# meccano_micro.net
KiCad netlist of a schematic drawn in EAGLE
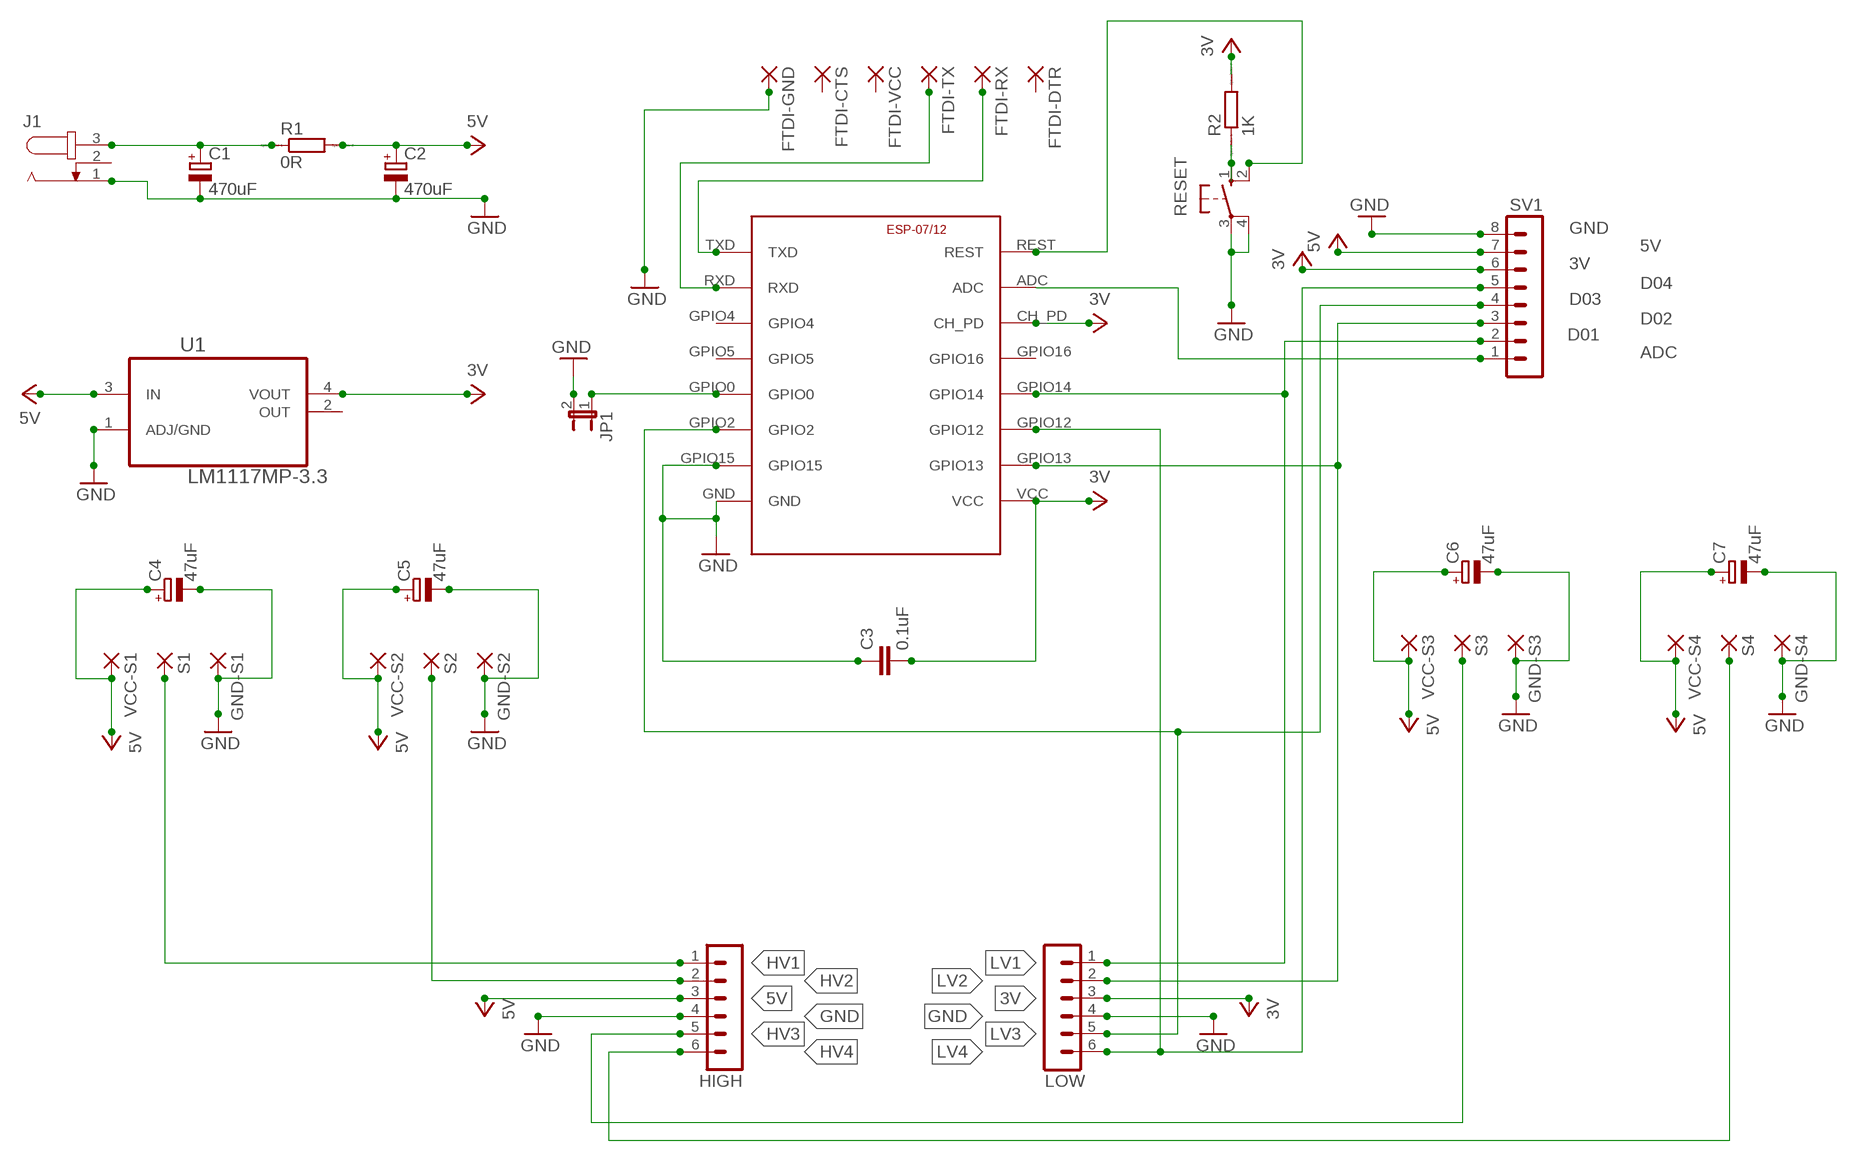
[diagram p0: schematic, sheet 1]

(export (version "E")
  (design (tool "Eeschema 10.0.6"))
  (components
    (comp (ref "C1")
      (value "470uF")
      (footprint "eagle-import:B45181B")
      (libsource (lib "eagle-import") (part "CPOL-EUB45181B"))
    )
    (comp (ref "C2")
      (value "470uF")
      (footprint "eagle-import:B45181B")
      (libsource (lib "eagle-import") (part "CPOL-EUB45181B"))
    )
    (comp (ref "C3")
      (value "0.1uF")
      (footprint "eagle-import:C2.5-4")
      (libsource (lib "eagle-import") (part "C2.5/4"))
    )
    (comp (ref "C4")
      (value "47uF")
      (footprint "eagle-import:B45181B")
      (libsource (lib "eagle-import") (part "CPOL-EUB45181B"))
    )
    (comp (ref "C5")
      (value "47uF")
      (footprint "eagle-import:B45181B")
      (libsource (lib "eagle-import") (part "CPOL-EUB45181B"))
    )
    (comp (ref "C6")
      (value "47uF")
      (footprint "eagle-import:B45181B")
      (libsource (lib "eagle-import") (part "CPOL-EUB45181B"))
    )
    (comp (ref "C7")
      (value "47uF")
      (footprint "eagle-import:B45181B")
      (libsource (lib "eagle-import") (part "CPOL-EUB45181B"))
    )
    (comp (ref "ESP-07/12")
      (value "ESP8266-07")
      (footprint "eagle-import:ESP-07")
      (libsource (lib "eagle-import") (part "ESP8266-07"))
    )
    (comp (ref "FTDI-CTS")
      (value "1,6/0,8")
      (footprint "eagle-import:1,6_0,8")
      (libsource (lib "eagle-import") (part "1,6/0,8"))
    )
    (comp (ref "FTDI-DTR")
      (value "1,6/0,8")
      (footprint "eagle-import:1,6_0,8")
      (libsource (lib "eagle-import") (part "1,6/0,8"))
    )
    (comp (ref "FTDI-GND")
      (value "1,6/0,8")
      (footprint "eagle-import:1,6_0,8")
      (libsource (lib "eagle-import") (part "1,6/0,8"))
    )
    (comp (ref "FTDI-RX")
      (value "1,6/0,8")
      (footprint "eagle-import:1,6_0,8")
      (libsource (lib "eagle-import") (part "1,6/0,8"))
    )
    (comp (ref "FTDI-TX")
      (value "1,6/0,8")
      (footprint "eagle-import:1,6_0,8")
      (libsource (lib "eagle-import") (part "1,6/0,8"))
    )
    (comp (ref "FTDI-VCC")
      (value "1,6/0,8")
      (footprint "eagle-import:1,6_0,8")
      (libsource (lib "eagle-import") (part "1,6/0,8"))
    )
    (comp (ref "GND-S1")
      (value "1,6/0,8")
      (footprint "eagle-import:1,6_0,8")
      (libsource (lib "eagle-import") (part "1,6/0,8"))
    )
    (comp (ref "GND-S2")
      (value "1,6/0,8")
      (footprint "eagle-import:1,6_0,8")
      (libsource (lib "eagle-import") (part "1,6/0,8"))
    )
    (comp (ref "GND-S3")
      (value "1,6/0,8")
      (footprint "eagle-import:1,6_0,8")
      (libsource (lib "eagle-import") (part "1,6/0,8"))
    )
    (comp (ref "GND-S4")
      (value "1,6/0,8")
      (footprint "eagle-import:1,6_0,8")
      (libsource (lib "eagle-import") (part "1,6/0,8"))
    )
    (comp (ref "HIGH")
      (value "MA06-1")
      (footprint "eagle-import:MA06-1")
      (libsource (lib "eagle-import") (part "MA06-1"))
    )
    (comp (ref "J1")
      (value "JACK-PLUG0")
      (footprint "eagle-import:SPC4077")
      (libsource (lib "eagle-import") (part "JACK-PLUG0"))
    )
    (comp (ref "JP1")
      (value "JP1E")
      (footprint "eagle-import:JP1")
      (libsource (lib "eagle-import") (part "JP1E"))
    )
    (comp (ref "LOW")
      (value "MA06-1")
      (footprint "eagle-import:MA06-1")
      (libsource (lib "eagle-import") (part "MA06-1"))
    )
    (comp (ref "R1")
      (value "0R")
      (footprint "eagle-import:0204_7")
      (libsource (lib "eagle-import") (part "R0204/7"))
    )
    (comp (ref "R2")
      (value "1K")
      (footprint "eagle-import:0204_7")
      (libsource (lib "eagle-import") (part "R0204/7"))
    )
    (comp (ref "RESET")
      (value "10-XX")
      (footprint "eagle-import:B3F-10XX")
      (fields (field (name "MPN") "B3F-1000"))
      (libsource (lib "eagle-import") (part "10-XX"))
    )
    (comp (ref "S1")
      (value "1,6/0,8")
      (footprint "eagle-import:1,6_0,8")
      (libsource (lib "eagle-import") (part "1,6/0,8"))
    )
    (comp (ref "S2")
      (value "1,6/0,8")
      (footprint "eagle-import:1,6_0,8")
      (libsource (lib "eagle-import") (part "1,6/0,8"))
    )
    (comp (ref "S3")
      (value "1,6/0,8")
      (footprint "eagle-import:1,6_0,8")
      (libsource (lib "eagle-import") (part "1,6/0,8"))
    )
    (comp (ref "S4")
      (value "1,6/0,8")
      (footprint "eagle-import:1,6_0,8")
      (libsource (lib "eagle-import") (part "1,6/0,8"))
    )
    (comp (ref "SV1")
      (value "MA08-1")
      (footprint "eagle-import:MA08-1")
      (libsource (lib "eagle-import") (part "MA08-1"))
    )
    (comp (ref "U1")
      (value "LM1117MP-3.3")
      (footprint "eagle-import:SOT230P696X180-4N")
      (libsource (lib "eagle-import") (part "LM1117MP-3.3"))
    )
    (comp (ref "VCC-S1")
      (value "1,6/0,8")
      (footprint "eagle-import:1,6_0,8")
      (libsource (lib "eagle-import") (part "1,6/0,8"))
    )
    (comp (ref "VCC-S2")
      (value "1,6/0,8")
      (footprint "eagle-import:1,6_0,8")
      (libsource (lib "eagle-import") (part "1,6/0,8"))
    )
    (comp (ref "VCC-S3")
      (value "1,6/0,8")
      (footprint "eagle-import:1,6_0,8")
      (libsource (lib "eagle-import") (part "1,6/0,8"))
    )
    (comp (ref "VCC-S4")
      (value "1,6/0,8")
      (footprint "eagle-import:1,6_0,8")
      (libsource (lib "eagle-import") (part "1,6/0,8"))
    )
  )
  (nets
    (net (code "1") (name "3V") (class "Default")
      (node (ref "C3") (pin "2") (pinfunction "2_2") (pintype "passive"))
      (node (ref "ESP-07/12") (pin "CH_PD") (pinfunction "CH_PD_CH_PD") (pintype "input"))
      (node (ref "ESP-07/12") (pin "VCC") (pinfunction "VCC_VCC") (pintype "power_in"))
      (node (ref "LOW") (pin "3") (pinfunction "3_3") (pintype "passive"))
      (node (ref "R2") (pin "1") (pinfunction "1_1") (pintype "passive"))
      (node (ref "R2") (pin "2") (pinfunction "2_2") (pintype "passive"))
      (node (ref "RESET") (pin "1") (pinfunction "S_1") (pintype "passive"))
      (node (ref "SV1") (pin "6") (pinfunction "6_6") (pintype "passive"))
      (node (ref "U1") (pin "4") (pinfunction "VOUT_4") (pintype "output"))
    )
    (net (code "2") (name "5V") (class "Default")
      (node (ref "C2") (pin "+") (pinfunction "+_+") (pintype "passive"))
      (node (ref "C4") (pin "+") (pinfunction "+_+") (pintype "passive"))
      (node (ref "C5") (pin "+") (pinfunction "+_+") (pintype "passive"))
      (node (ref "C6") (pin "+") (pinfunction "+_+") (pintype "passive"))
      (node (ref "C7") (pin "+") (pinfunction "+_+") (pintype "passive"))
      (node (ref "HIGH") (pin "3") (pinfunction "3_3") (pintype "passive"))
      (node (ref "R1") (pin "2") (pinfunction "2_2") (pintype "passive"))
      (node (ref "SV1") (pin "7") (pinfunction "7_7") (pintype "passive"))
      (node (ref "U1") (pin "3") (pinfunction "IN_3") (pintype "input"))
      (node (ref "VCC-S1") (pin "1") (pinfunction "P_1") (pintype "passive"))
      (node (ref "VCC-S2") (pin "1") (pinfunction "P_1") (pintype "passive"))
      (node (ref "VCC-S3") (pin "1") (pinfunction "P_1") (pintype "passive"))
      (node (ref "VCC-S4") (pin "1") (pinfunction "P_1") (pintype "passive"))
    )
    (net (code "3") (name "GND") (class "Default")
      (node (ref "C1") (pin "-") (pinfunction "-_-") (pintype "passive"))
      (node (ref "C2") (pin "-") (pinfunction "-_-") (pintype "passive"))
      (node (ref "C3") (pin "1") (pinfunction "1_1") (pintype "passive"))
      (node (ref "C4") (pin "-") (pinfunction "-_-") (pintype "passive"))
      (node (ref "C5") (pin "-") (pinfunction "-_-") (pintype "passive"))
      (node (ref "C6") (pin "-") (pinfunction "-_-") (pintype "passive"))
      (node (ref "C7") (pin "-") (pinfunction "-_-") (pintype "passive"))
      (node (ref "ESP-07/12") (pin "GND") (pinfunction "GND_GND") (pintype "power_in"))
      (node (ref "ESP-07/12") (pin "GPIO15") (pinfunction "GPIO15_GPIO15") (pintype "input"))
      (node (ref "FTDI-GND") (pin "1") (pinfunction "P_1") (pintype "passive"))
      (node (ref "GND-S1") (pin "1") (pinfunction "P_1") (pintype "passive"))
      (node (ref "GND-S2") (pin "1") (pinfunction "P_1") (pintype "passive"))
      (node (ref "GND-S3") (pin "1") (pinfunction "P_1") (pintype "passive"))
      (node (ref "GND-S4") (pin "1") (pinfunction "P_1") (pintype "passive"))
      (node (ref "HIGH") (pin "4") (pinfunction "4_4") (pintype "passive"))
      (node (ref "J1") (pin "1") (pinfunction "1_1") (pintype "passive"))
      (node (ref "JP1") (pin "2") (pinfunction "2_2") (pintype "passive"))
      (node (ref "LOW") (pin "4") (pinfunction "4_4") (pintype "passive"))
      (node (ref "RESET") (pin "3") (pinfunction "P_3") (pintype "passive"))
      (node (ref "RESET") (pin "4") (pinfunction "P1_4") (pintype "passive"))
      (node (ref "SV1") (pin "8") (pinfunction "8_8") (pintype "passive"))
      (node (ref "U1") (pin "1") (pinfunction "ADJ/GND_1") (pintype "passive"))
    )
    (net (code "4") (name "HV1") (class "Default")
      (node (ref "HIGH") (pin "1") (pinfunction "1_1") (pintype "passive"))
      (node (ref "S1") (pin "1") (pinfunction "P_1") (pintype "passive"))
    )
    (net (code "5") (name "HV2") (class "Default")
      (node (ref "HIGH") (pin "2") (pinfunction "2_2") (pintype "passive"))
      (node (ref "S2") (pin "1") (pinfunction "P_1") (pintype "passive"))
    )
    (net (code "6") (name "HV3") (class "Default")
      (node (ref "HIGH") (pin "5") (pinfunction "5_5") (pintype "passive"))
      (node (ref "S3") (pin "1") (pinfunction "P_1") (pintype "passive"))
    )
    (net (code "7") (name "HV4") (class "Default")
      (node (ref "HIGH") (pin "6") (pinfunction "6_6") (pintype "passive"))
      (node (ref "S4") (pin "1") (pinfunction "P_1") (pintype "passive"))
    )
    (net (code "8") (name "LV1") (class "Default")
      (node (ref "ESP-07/12") (pin "GPIO14") (pinfunction "GPIO14_GPIO14") (pintype "bidirectional"))
      (node (ref "LOW") (pin "1") (pinfunction "1_1") (pintype "passive"))
      (node (ref "SV1") (pin "2") (pinfunction "2_2") (pintype "passive"))
    )
    (net (code "9") (name "LV2") (class "Default")
      (node (ref "ESP-07/12") (pin "GPIO13") (pinfunction "GPIO13_GPIO13") (pintype "bidirectional"))
      (node (ref "LOW") (pin "2") (pinfunction "2_2") (pintype "passive"))
      (node (ref "SV1") (pin "3") (pinfunction "3_3") (pintype "passive"))
    )
    (net (code "10") (name "LV3") (class "Default")
      (node (ref "ESP-07/12") (pin "GPIO2") (pinfunction "GPIO2_GPIO2") (pintype "bidirectional"))
      (node (ref "LOW") (pin "5") (pinfunction "5_5") (pintype "passive"))
      (node (ref "SV1") (pin "4") (pinfunction "4_4") (pintype "passive"))
    )
    (net (code "11") (name "LV4") (class "Default")
      (node (ref "ESP-07/12") (pin "GPIO12") (pinfunction "GPIO12_GPIO12") (pintype "bidirectional"))
      (node (ref "LOW") (pin "6") (pinfunction "6_6") (pintype "passive"))
      (node (ref "SV1") (pin "5") (pinfunction "5_5") (pintype "passive"))
    )
    (net (code "12") (name "Net-(C1-Pad+)") (class "Default")
      (node (ref "C1") (pin "+") (pinfunction "+_+") (pintype "passive"))
      (node (ref "J1") (pin "3") (pinfunction "3_3") (pintype "passive"))
      (node (ref "R1") (pin "1") (pinfunction "1_1") (pintype "passive"))
    )
    (net (code "13") (name "Net-(ESP-07/12-PadADC)") (class "Default")
      (node (ref "ESP-07/12") (pin "ADC") (pinfunction "ADC_ADC") (pintype "bidirectional"))
      (node (ref "SV1") (pin "1") (pinfunction "1_1") (pintype "passive"))
    )
    (net (code "14") (name "Net-(ESP-07/12-PadGPIO0)") (class "Default")
      (node (ref "ESP-07/12") (pin "GPIO0") (pinfunction "GPIO0_GPIO0") (pintype "bidirectional"))
      (node (ref "JP1") (pin "1") (pinfunction "1_1") (pintype "passive"))
    )
    (net (code "15") (name "Net-(FTDI-RX-P)") (class "Default")
      (node (ref "ESP-07/12") (pin "TXD") (pinfunction "TXD_TXD") (pintype "output"))
      (node (ref "FTDI-RX") (pin "1") (pinfunction "P_1") (pintype "passive"))
    )
    (net (code "16") (name "Net-(FTDI-TX-P)") (class "Default")
      (node (ref "ESP-07/12") (pin "RXD") (pinfunction "RXD_RXD") (pintype "input"))
      (node (ref "FTDI-TX") (pin "1") (pinfunction "P_1") (pintype "passive"))
    )
    (net (code "17") (name "Net-(RESET-S1)") (class "Default")
      (node (ref "ESP-07/12") (pin "REST") (pinfunction "REST_REST") (pintype "bidirectional"))
      (node (ref "RESET") (pin "2") (pinfunction "S1_2") (pintype "passive"))
    )
    (net (code "18") (name "unconnected-(ESP-07/12-PadGPIO4)") (class "Default")
      (node (ref "ESP-07/12") (pin "GPIO4") (pinfunction "GPIO4_GPIO4") (pintype "bidirectional"))
    )
    (net (code "19") (name "unconnected-(ESP-07/12-PadGPIO5)") (class "Default")
      (node (ref "ESP-07/12") (pin "GPIO5") (pinfunction "GPIO5_GPIO5") (pintype "bidirectional"))
    )
    (net (code "20") (name "unconnected-(ESP-07/12-PadGPIO16)") (class "Default")
      (node (ref "ESP-07/12") (pin "GPIO16") (pinfunction "GPIO16_GPIO16") (pintype "bidirectional"))
    )
    (net (code "21") (name "unconnected-(FTDI-CTS-P-Pad1)") (class "Default")
      (node (ref "FTDI-CTS") (pin "1") (pinfunction "P_1") (pintype "passive"))
    )
    (net (code "22") (name "unconnected-(FTDI-DTR-P-Pad1)") (class "Default")
      (node (ref "FTDI-DTR") (pin "1") (pinfunction "P_1") (pintype "passive"))
    )
    (net (code "23") (name "unconnected-(FTDI-VCC-P-Pad1)") (class "Default")
      (node (ref "FTDI-VCC") (pin "1") (pinfunction "P_1") (pintype "passive"))
    )
    (net (code "24") (name "unconnected-(J1-Pad2)") (class "Default")
      (node (ref "J1") (pin "2") (pinfunction "2_2") (pintype "passive"))
    )
    (net (code "25") (name "unconnected-(U1-OUT-Pad2)") (class "Default")
      (node (ref "U1") (pin "2") (pinfunction "OUT_2") (pintype "output"))
    )
  )
)
